# wifi.net
KiCad netlist of a schematic drawn in Altium Designer
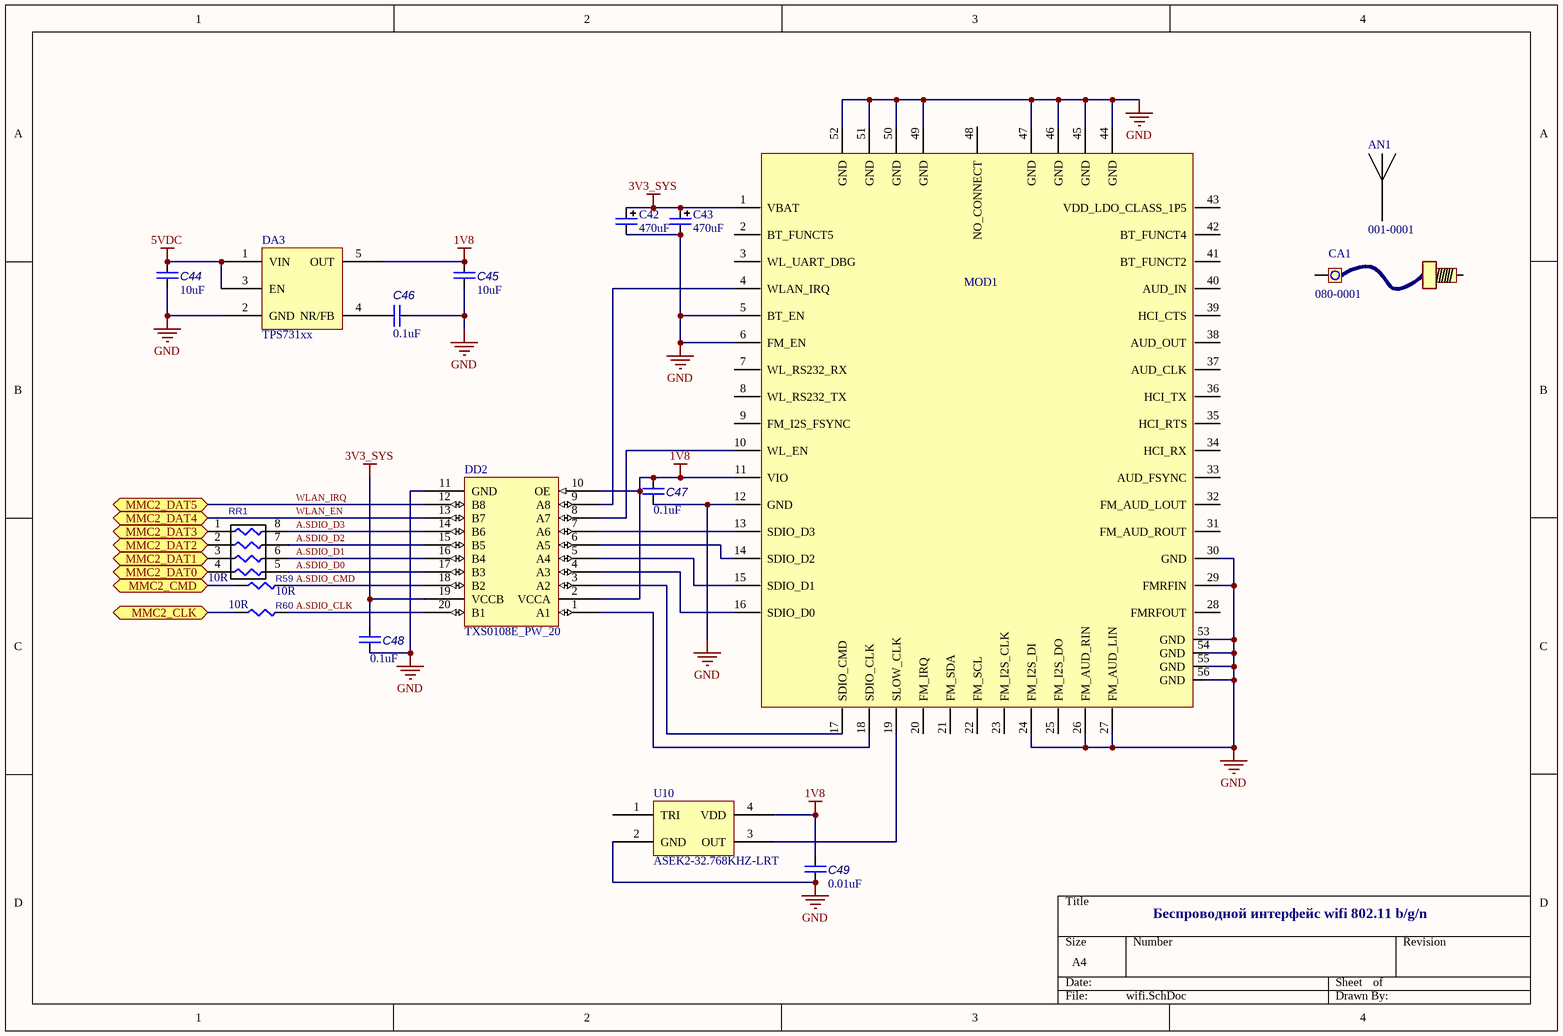
[diagram p0: wifi.SchDoc]

(export (version "E")
  (design (tool "Eeschema 10.0.6"))
  (components
    (comp (ref "AN1")
      (value "Antenna")
      (fields (field (name "P/N") "001-0001"))
      (libsource (lib "spider") (part "Antenna"))
    )
    (comp (ref "C42")
      (value "470uF")
      (footprint "Cap_D")
      (description "Tantalum Capacitor Case D")
      (fields (field (name "Comment") "Cap_D"))
      (libsource (lib "spider") (part "Cap_D"))
    )
    (comp (ref "C43")
      (value "470uF")
      (footprint "Cap_D")
      (description "Tantalum Capacitor Case D")
      (fields (field (name "Comment") "Cap_D"))
      (libsource (lib "spider") (part "Cap_D"))
    )
    (comp (ref "C44")
      (value "10uF")
      (footprint "CC2012-0805")
      (description "C0805")
      (libsource (lib "am335x-base") (part "C0805"))
    )
    (comp (ref "C45")
      (value "10uF")
      (footprint "CC2012-0805")
      (description "C0805")
      (libsource (lib "am335x-base") (part "C0805"))
    )
    (comp (ref "C46")
      (value "0.1uF")
      (footprint "CC1608-0603")
      (description "C0603")
      (libsource (lib "spider") (part "C0603"))
    )
    (comp (ref "C47")
      (value "0.1uF")
      (footprint "CC1608-0603")
      (description "C0603")
      (libsource (lib "spider") (part "C0603"))
    )
    (comp (ref "C48")
      (value "0.1uF")
      (footprint "CC1608-0603")
      (description "C0603")
      (libsource (lib "spider") (part "C0603"))
    )
    (comp (ref "C49")
      (value "0.01uF")
      (footprint "CC1608-0603")
      (description "C0603")
      (libsource (lib "spider") (part "C0603"))
    )
    (comp (ref "CA1")
      (value "Cable")
      (description "Wifi Cable")
      (fields (field (name "P/N") "080-0001"))
      (libsource (lib "spider") (part "Cable"))
    )
    (comp (ref "DA3")
      (value "TPS731xx")
      (footprint "SOT95P280X145-5N")
      (description "Cap-Free, NMOS, 150mA LDO")
      (fields (field (name "MANUFACTURER") "TI"))
      (libsource (lib "spider") (part "TPS731xx"))
    )
    (comp (ref "DD2")
      (value "TXS0108E_PW_20")
      (footprint "PW20")
      (description "Imported")
      (fields
        (field (name "MANUFACTURER_PART_NUMBER") "txs0108e_pw_20")
        (field (name "MANUFACTURER") "Texas Instruments")
      )
      (libsource (lib "spider") (part "TXS0108E_PW_20"))
    )
    (comp (ref "MOD1")
      (value "TIWI-R2_MODULE_UFL")
      (footprint "tiwi-r2")
      (description "TiWi-R2 with u.fl Module")
      (fields (field (name "MANUFACTURER") "LSR"))
      (libsource (lib "spider") (part "TIWI-R2_MODULE_UFL"))
    )
    (comp (ref "R59")
      (value "10R")
      (footprint "RESC1608X55N")
      (description "R0603")
      (libsource (lib "spider") (part "R0603"))
    )
    (comp (ref "R60")
      (value "10R")
      (footprint "RESC1608X55N")
      (description "R0603")
      (libsource (lib "spider") (part "R0603"))
    )
    (comp (ref "RR1")
      (value "10R")
      (footprint "CAY16-J4")
      (description "Resistor network 4x")
      (fields (field (name "Comment") "CAY-J4"))
      (libsource (lib "spider") (part "CAY-J4"))
    )
    (comp (ref "U10")
      (value "ASEK2-32.768KHZ-LRT")
      (footprint "asek1")
      (description "32.768KHZ 1.8V oscillator")
      (fields (field (name "MANUFACTURER") "Abracon"))
      (libsource (lib "spider") (part "ASEK2-32.768KHZ-LRT"))
    )
  )
  (nets
    (net (code "1") (name "/A.SDIO_CLK") (class "Default")
      (node (ref "DD2") (pin "20") (pinfunction "B1_20") (pintype "bidirectional"))
      (node (ref "R60") (pin "2") (pinfunction "2_2") (pintype "passive"))
    )
    (net (code "2") (name "/A.SDIO_CMD") (class "Default")
      (node (ref "DD2") (pin "18") (pinfunction "B2_18") (pintype "bidirectional"))
      (node (ref "R59") (pin "2") (pinfunction "2_2") (pintype "passive"))
    )
    (net (code "3") (name "/A.SDIO_D0") (class "Default")
      (node (ref "DD2") (pin "17") (pinfunction "B3_17") (pintype "bidirectional"))
      (node (ref "RR1") (pin "5") (pintype "passive"))
    )
    (net (code "4") (name "/A.SDIO_D1") (class "Default")
      (node (ref "DD2") (pin "16") (pinfunction "B4_16") (pintype "bidirectional"))
      (node (ref "RR1") (pin "6") (pintype "passive"))
    )
    (net (code "5") (name "/A.SDIO_D2") (class "Default")
      (node (ref "DD2") (pin "15") (pinfunction "B5_15") (pintype "bidirectional"))
      (node (ref "RR1") (pin "7") (pintype "passive"))
    )
    (net (code "6") (name "/A.SDIO_D3") (class "Default")
      (node (ref "DD2") (pin "14") (pinfunction "B6_14") (pintype "bidirectional"))
      (node (ref "RR1") (pin "8") (pintype "passive"))
    )
    (net (code "7") (name "/MMC2_CLK") (class "Default")
      (node (ref "R60") (pin "1") (pinfunction "1_1") (pintype "passive"))
    )
    (net (code "8") (name "/MMC2_CMD") (class "Default")
      (node (ref "R59") (pin "1") (pinfunction "1_1") (pintype "passive"))
    )
    (net (code "9") (name "/MMC2_DAT0") (class "Default") (node (ref "RR1") (pin "4") (pintype "passive")))
    (net (code "10") (name "/MMC2_DAT1") (class "Default") (node (ref "RR1") (pin "3") (pintype "passive")))
    (net (code "11") (name "/MMC2_DAT2") (class "Default") (node (ref "RR1") (pin "2") (pintype "passive")))
    (net (code "12") (name "/MMC2_DAT3") (class "Default") (node (ref "RR1") (pin "1") (pintype "passive")))
    (net (code "13") (name "/WLAN_EN") (class "Default")
      (node (ref "DD2") (pin "13") (pinfunction "B7_13") (pintype "bidirectional"))
    )
    (net (code "14") (name "/WLAN_IRQ") (class "Default")
      (node (ref "DD2") (pin "12") (pinfunction "B8_12") (pintype "bidirectional"))
    )
    (net (code "15") (name "1V8") (class "Default")
      (node (ref "C45") (pin "2") (pinfunction "2_2") (pintype "passive"))
      (node (ref "C47") (pin "2") (pinfunction "2_2") (pintype "passive"))
      (node (ref "C49") (pin "1") (pinfunction "1_1") (pintype "passive"))
      (node (ref "DA3") (pin "5") (pinfunction "OUT_5") (pintype "passive"))
      (node (ref "DD2") (pin "10") (pinfunction "OE_10") (pintype "input"))
      (node (ref "DD2") (pin "2") (pinfunction "VCCA_2") (pintype "power_in"))
      (node (ref "MOD1") (pin "11") (pinfunction "VIO_11") (pintype "passive"))
      (node (ref "U10") (pin "4") (pinfunction "VDD_4") (pintype "passive"))
    )
    (net (code "16") (name "3V3_SYS") (class "Default")
      (node (ref "C42") (pin "1") (pinfunction "1_1") (pintype "passive"))
      (node (ref "C43") (pin "1") (pinfunction "1_1") (pintype "passive"))
      (node (ref "C48") (pin "2") (pinfunction "2_2") (pintype "passive"))
      (node (ref "DD2") (pin "19") (pinfunction "VCCB_19") (pintype "power_in"))
      (node (ref "MOD1") (pin "1") (pinfunction "VBAT_1") (pintype "passive"))
    )
    (net (code "17") (name "5VDC") (class "Default")
      (node (ref "C44") (pin "2") (pinfunction "2_2") (pintype "passive"))
      (node (ref "DA3") (pin "1") (pinfunction "VIN_1") (pintype "passive"))
      (node (ref "DA3") (pin "3") (pinfunction "EN_3") (pintype "passive"))
    )
    (net (code "18") (name "GND") (class "Default")
      (node (ref "C42") (pin "2") (pinfunction "2_2") (pintype "passive"))
      (node (ref "C43") (pin "2") (pinfunction "2_2") (pintype "passive"))
      (node (ref "C44") (pin "1") (pinfunction "1_1") (pintype "passive"))
      (node (ref "C45") (pin "1") (pinfunction "1_1") (pintype "passive"))
      (node (ref "C46") (pin "1") (pinfunction "1_1") (pintype "passive"))
      (node (ref "C47") (pin "1") (pinfunction "1_1") (pintype "passive"))
      (node (ref "C48") (pin "1") (pinfunction "1_1") (pintype "passive"))
      (node (ref "C49") (pin "2") (pinfunction "2_2") (pintype "passive"))
      (node (ref "DA3") (pin "2") (pinfunction "GND_2") (pintype "passive"))
      (node (ref "DD2") (pin "11") (pinfunction "GND_11") (pintype "power_in"))
      (node (ref "MOD1") (pin "12") (pinfunction "GND_12") (pintype "passive"))
      (node (ref "MOD1") (pin "24") (pinfunction "FM_I2S_DI_24") (pintype "passive"))
      (node (ref "MOD1") (pin "26") (pinfunction "FM_AUD_RIN_26") (pintype "passive"))
      (node (ref "MOD1") (pin "27") (pinfunction "FM_AUD_LIN_27") (pintype "passive"))
      (node (ref "MOD1") (pin "29") (pinfunction "FMRFIN_29") (pintype "passive"))
      (node (ref "MOD1") (pin "30") (pinfunction "GND_30") (pintype "passive"))
      (node (ref "MOD1") (pin "44") (pinfunction "GND_44") (pintype "passive"))
      (node (ref "MOD1") (pin "45") (pinfunction "GND_45") (pintype "passive"))
      (node (ref "MOD1") (pin "46") (pinfunction "GND_46") (pintype "passive"))
      (node (ref "MOD1") (pin "47") (pinfunction "GND_47") (pintype "passive"))
      (node (ref "MOD1") (pin "49") (pinfunction "GND_49") (pintype "passive"))
      (node (ref "MOD1") (pin "5") (pinfunction "BT_EN_5") (pintype "passive"))
      (node (ref "MOD1") (pin "50") (pinfunction "GND_50") (pintype "passive"))
      (node (ref "MOD1") (pin "51") (pinfunction "GND_51") (pintype "passive"))
      (node (ref "MOD1") (pin "52") (pinfunction "GND_52") (pintype "passive"))
      (node (ref "MOD1") (pin "53") (pinfunction "GND_53") (pintype "passive"))
      (node (ref "MOD1") (pin "54") (pinfunction "GND_54") (pintype "passive"))
      (node (ref "MOD1") (pin "55") (pinfunction "GND_55") (pintype "passive"))
      (node (ref "MOD1") (pin "56") (pinfunction "GND_56") (pintype "passive"))
      (node (ref "MOD1") (pin "6") (pinfunction "FM_EN_6") (pintype "passive"))
      (node (ref "U10") (pin "2") (pinfunction "GND_2") (pintype "passive"))
    )
    (net (code "19") (name "Net-(DA3-NR{slash}FB)") (class "Default")
      (node (ref "C46") (pin "2") (pinfunction "2_2") (pintype "passive"))
      (node (ref "DA3") (pin "4") (pinfunction "NR/FB_4") (pintype "passive"))
    )
    (net (code "20") (name "Net-(DD2-A1)") (class "Default")
      (node (ref "DD2") (pin "1") (pinfunction "A1_1") (pintype "bidirectional"))
      (node (ref "MOD1") (pin "18") (pinfunction "SDIO_CLK_18") (pintype "passive"))
    )
    (net (code "21") (name "Net-(DD2-A2)") (class "Default")
      (node (ref "DD2") (pin "3") (pinfunction "A2_3") (pintype "bidirectional"))
      (node (ref "MOD1") (pin "17") (pinfunction "SDIO_CMD_17") (pintype "passive"))
    )
    (net (code "22") (name "Net-(DD2-A3)") (class "Default")
      (node (ref "DD2") (pin "4") (pinfunction "A3_4") (pintype "bidirectional"))
      (node (ref "MOD1") (pin "16") (pinfunction "SDIO_D0_16") (pintype "passive"))
    )
    (net (code "23") (name "Net-(DD2-A4)") (class "Default")
      (node (ref "DD2") (pin "5") (pinfunction "A4_5") (pintype "bidirectional"))
      (node (ref "MOD1") (pin "15") (pinfunction "SDIO_D1_15") (pintype "passive"))
    )
    (net (code "24") (name "Net-(DD2-A5)") (class "Default")
      (node (ref "DD2") (pin "6") (pinfunction "A5_6") (pintype "bidirectional"))
      (node (ref "MOD1") (pin "14") (pinfunction "SDIO_D2_14") (pintype "passive"))
    )
    (net (code "25") (name "Net-(DD2-A6)") (class "Default")
      (node (ref "DD2") (pin "7") (pinfunction "A6_7") (pintype "bidirectional"))
      (node (ref "MOD1") (pin "13") (pinfunction "SDIO_D3_13") (pintype "passive"))
    )
    (net (code "26") (name "Net-(DD2-A7)") (class "Default")
      (node (ref "DD2") (pin "8") (pinfunction "A7_8") (pintype "bidirectional"))
      (node (ref "MOD1") (pin "10") (pinfunction "WL_EN_10") (pintype "passive"))
    )
    (net (code "27") (name "Net-(DD2-A8)") (class "Default")
      (node (ref "DD2") (pin "9") (pinfunction "A8_9") (pintype "bidirectional"))
      (node (ref "MOD1") (pin "4") (pinfunction "WLAN_IRQ_4") (pintype "passive"))
    )
    (net (code "28") (name "Net-(MOD1-SLOW_CLK)") (class "Default")
      (node (ref "MOD1") (pin "19") (pinfunction "SLOW_CLK_19") (pintype "passive"))
      (node (ref "U10") (pin "3") (pinfunction "OUT_3") (pintype "passive"))
    )
    (net (code "29") (name "unconnected-(AN1-Pad1)") (class "Default")
      (node (ref "AN1") (pin "1") (pinfunction "1_1") (pintype "passive"))
    )
    (net (code "30") (name "unconnected-(CA1-Pad1)") (class "Default")
      (node (ref "CA1") (pin "1") (pinfunction "1_1") (pintype "passive"))
    )
    (net (code "31") (name "unconnected-(CA1-Pad2)") (class "Default")
      (node (ref "CA1") (pin "2") (pinfunction "2_2") (pintype "passive"))
    )
    (net (code "32") (name "unconnected-(MOD1-AUD_CLK-Pad37)") (class "Default")
      (node (ref "MOD1") (pin "37") (pinfunction "AUD_CLK_37") (pintype "passive"))
    )
    (net (code "33") (name "unconnected-(MOD1-AUD_FSYNC-Pad33)") (class "Default")
      (node (ref "MOD1") (pin "33") (pinfunction "AUD_FSYNC_33") (pintype "passive"))
    )
    (net (code "34") (name "unconnected-(MOD1-AUD_IN-Pad40)") (class "Default")
      (node (ref "MOD1") (pin "40") (pinfunction "AUD_IN_40") (pintype "passive"))
    )
    (net (code "35") (name "unconnected-(MOD1-AUD_OUT-Pad38)") (class "Default")
      (node (ref "MOD1") (pin "38") (pinfunction "AUD_OUT_38") (pintype "passive"))
    )
    (net (code "36") (name "unconnected-(MOD1-BT_FUNCT2-Pad41)") (class "Default")
      (node (ref "MOD1") (pin "41") (pinfunction "BT_FUNCT2_41") (pintype "passive"))
    )
    (net (code "37") (name "unconnected-(MOD1-BT_FUNCT4-Pad42)") (class "Default")
      (node (ref "MOD1") (pin "42") (pinfunction "BT_FUNCT4_42") (pintype "passive"))
    )
    (net (code "38") (name "unconnected-(MOD1-BT_FUNCT5-Pad2)") (class "Default")
      (node (ref "MOD1") (pin "2") (pinfunction "BT_FUNCT5_2") (pintype "passive"))
    )
    (net (code "39") (name "unconnected-(MOD1-FMRFOUT-Pad28)") (class "Default")
      (node (ref "MOD1") (pin "28") (pinfunction "FMRFOUT_28") (pintype "passive"))
    )
    (net (code "40") (name "unconnected-(MOD1-FM_AUD_LOUT-Pad32)") (class "Default")
      (node (ref "MOD1") (pin "32") (pinfunction "FM_AUD_LOUT_32") (pintype "passive"))
    )
    (net (code "41") (name "unconnected-(MOD1-FM_AUD_ROUT-Pad31)") (class "Default")
      (node (ref "MOD1") (pin "31") (pinfunction "FM_AUD_ROUT_31") (pintype "passive"))
    )
    (net (code "42") (name "unconnected-(MOD1-FM_I2S_CLK-Pad23)") (class "Default")
      (node (ref "MOD1") (pin "23") (pinfunction "FM_I2S_CLK_23") (pintype "passive"))
    )
    (net (code "43") (name "unconnected-(MOD1-FM_I2S_DO-Pad25)") (class "Default")
      (node (ref "MOD1") (pin "25") (pinfunction "FM_I2S_DO_25") (pintype "passive"))
    )
    (net (code "44") (name "unconnected-(MOD1-FM_I2S_FSYNC-Pad9)") (class "Default")
      (node (ref "MOD1") (pin "9") (pinfunction "FM_I2S_FSYNC_9") (pintype "passive"))
    )
    (net (code "45") (name "unconnected-(MOD1-FM_IRQ-Pad20)") (class "Default")
      (node (ref "MOD1") (pin "20") (pinfunction "FM_IRQ_20") (pintype "passive"))
    )
    (net (code "46") (name "unconnected-(MOD1-FM_SCL-Pad22)") (class "Default")
      (node (ref "MOD1") (pin "22") (pinfunction "FM_SCL_22") (pintype "passive"))
    )
    (net (code "47") (name "unconnected-(MOD1-FM_SDA-Pad21)") (class "Default")
      (node (ref "MOD1") (pin "21") (pinfunction "FM_SDA_21") (pintype "passive"))
    )
    (net (code "48") (name "unconnected-(MOD1-HCI_CTS-Pad39)") (class "Default")
      (node (ref "MOD1") (pin "39") (pinfunction "HCI_CTS_39") (pintype "passive"))
    )
    (net (code "49") (name "unconnected-(MOD1-HCI_RTS-Pad35)") (class "Default")
      (node (ref "MOD1") (pin "35") (pinfunction "HCI_RTS_35") (pintype "passive"))
    )
    (net (code "50") (name "unconnected-(MOD1-HCI_RX-Pad34)") (class "Default")
      (node (ref "MOD1") (pin "34") (pinfunction "HCI_RX_34") (pintype "passive"))
    )
    (net (code "51") (name "unconnected-(MOD1-HCI_TX-Pad36)") (class "Default")
      (node (ref "MOD1") (pin "36") (pinfunction "HCI_TX_36") (pintype "passive"))
    )
    (net (code "52") (name "unconnected-(MOD1-NO_CONNECT-Pad48)") (class "Default")
      (node (ref "MOD1") (pin "48") (pinfunction "NO_CONNECT_48") (pintype "passive"))
    )
    (net (code "53") (name "unconnected-(MOD1-VDD_LDO_CLASS_1P5-Pad43)") (class "Default")
      (node (ref "MOD1") (pin "43") (pinfunction "VDD_LDO_CLASS_1P5_43") (pintype "passive"))
    )
    (net (code "54") (name "unconnected-(MOD1-WL_RS232_RX-Pad7)") (class "Default")
      (node (ref "MOD1") (pin "7") (pinfunction "WL_RS232_RX_7") (pintype "passive"))
    )
    (net (code "55") (name "unconnected-(MOD1-WL_RS232_TX-Pad8)") (class "Default")
      (node (ref "MOD1") (pin "8") (pinfunction "WL_RS232_TX_8") (pintype "passive"))
    )
    (net (code "56") (name "unconnected-(MOD1-WL_UART_DBG-Pad3)") (class "Default")
      (node (ref "MOD1") (pin "3") (pinfunction "WL_UART_DBG_3") (pintype "passive"))
    )
    (net (code "57") (name "unconnected-(U10-TRI-Pad1)") (class "Default")
      (node (ref "U10") (pin "1") (pinfunction "TRI_1") (pintype "passive"))
    )
  )
)
